# BSPD.net
KiCad netlist of a schematic drawn in Altium Designer
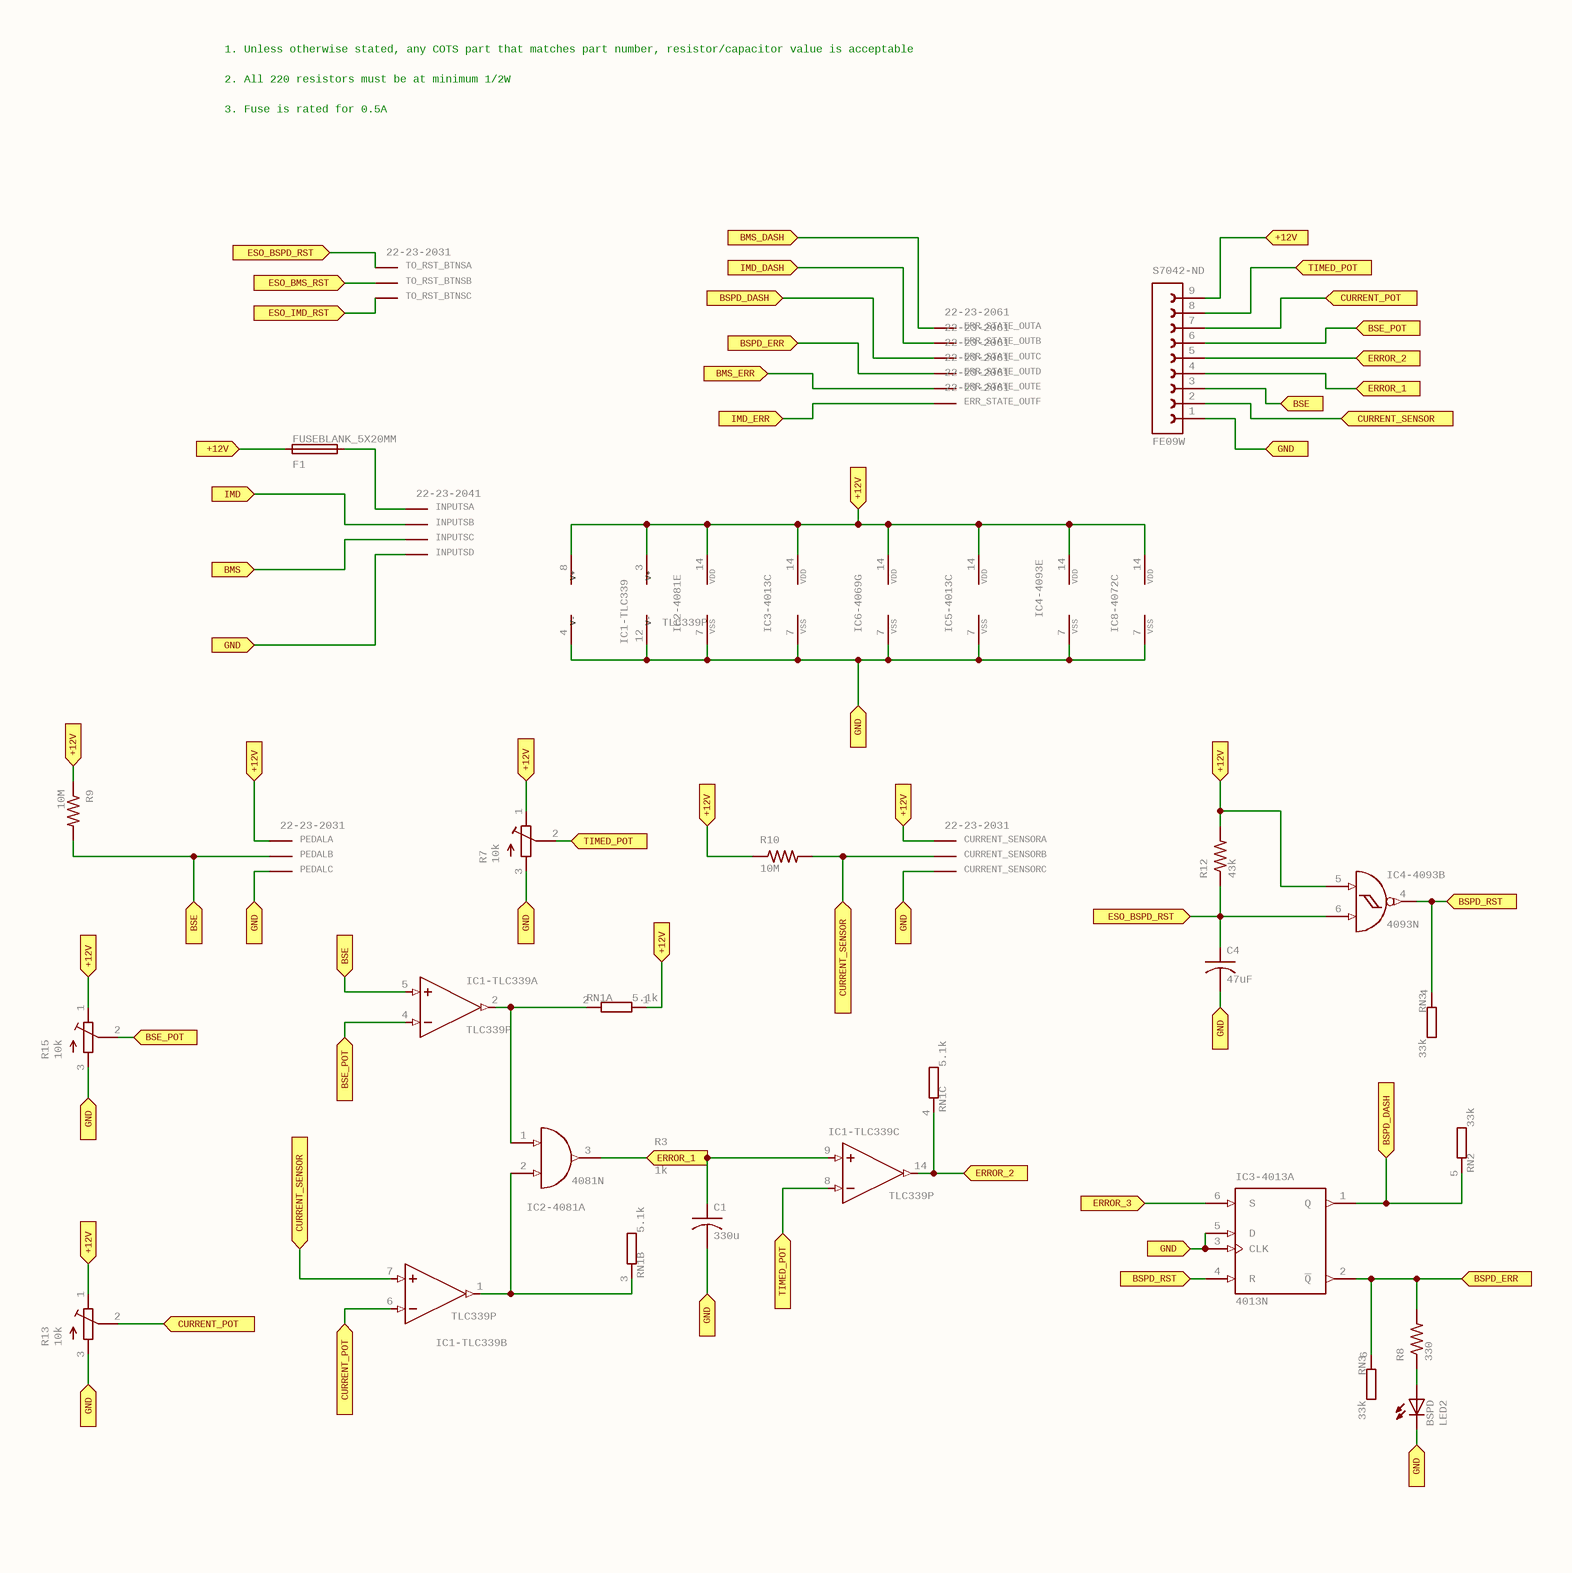
[diagram p0: BSPD.SchDoc, left]
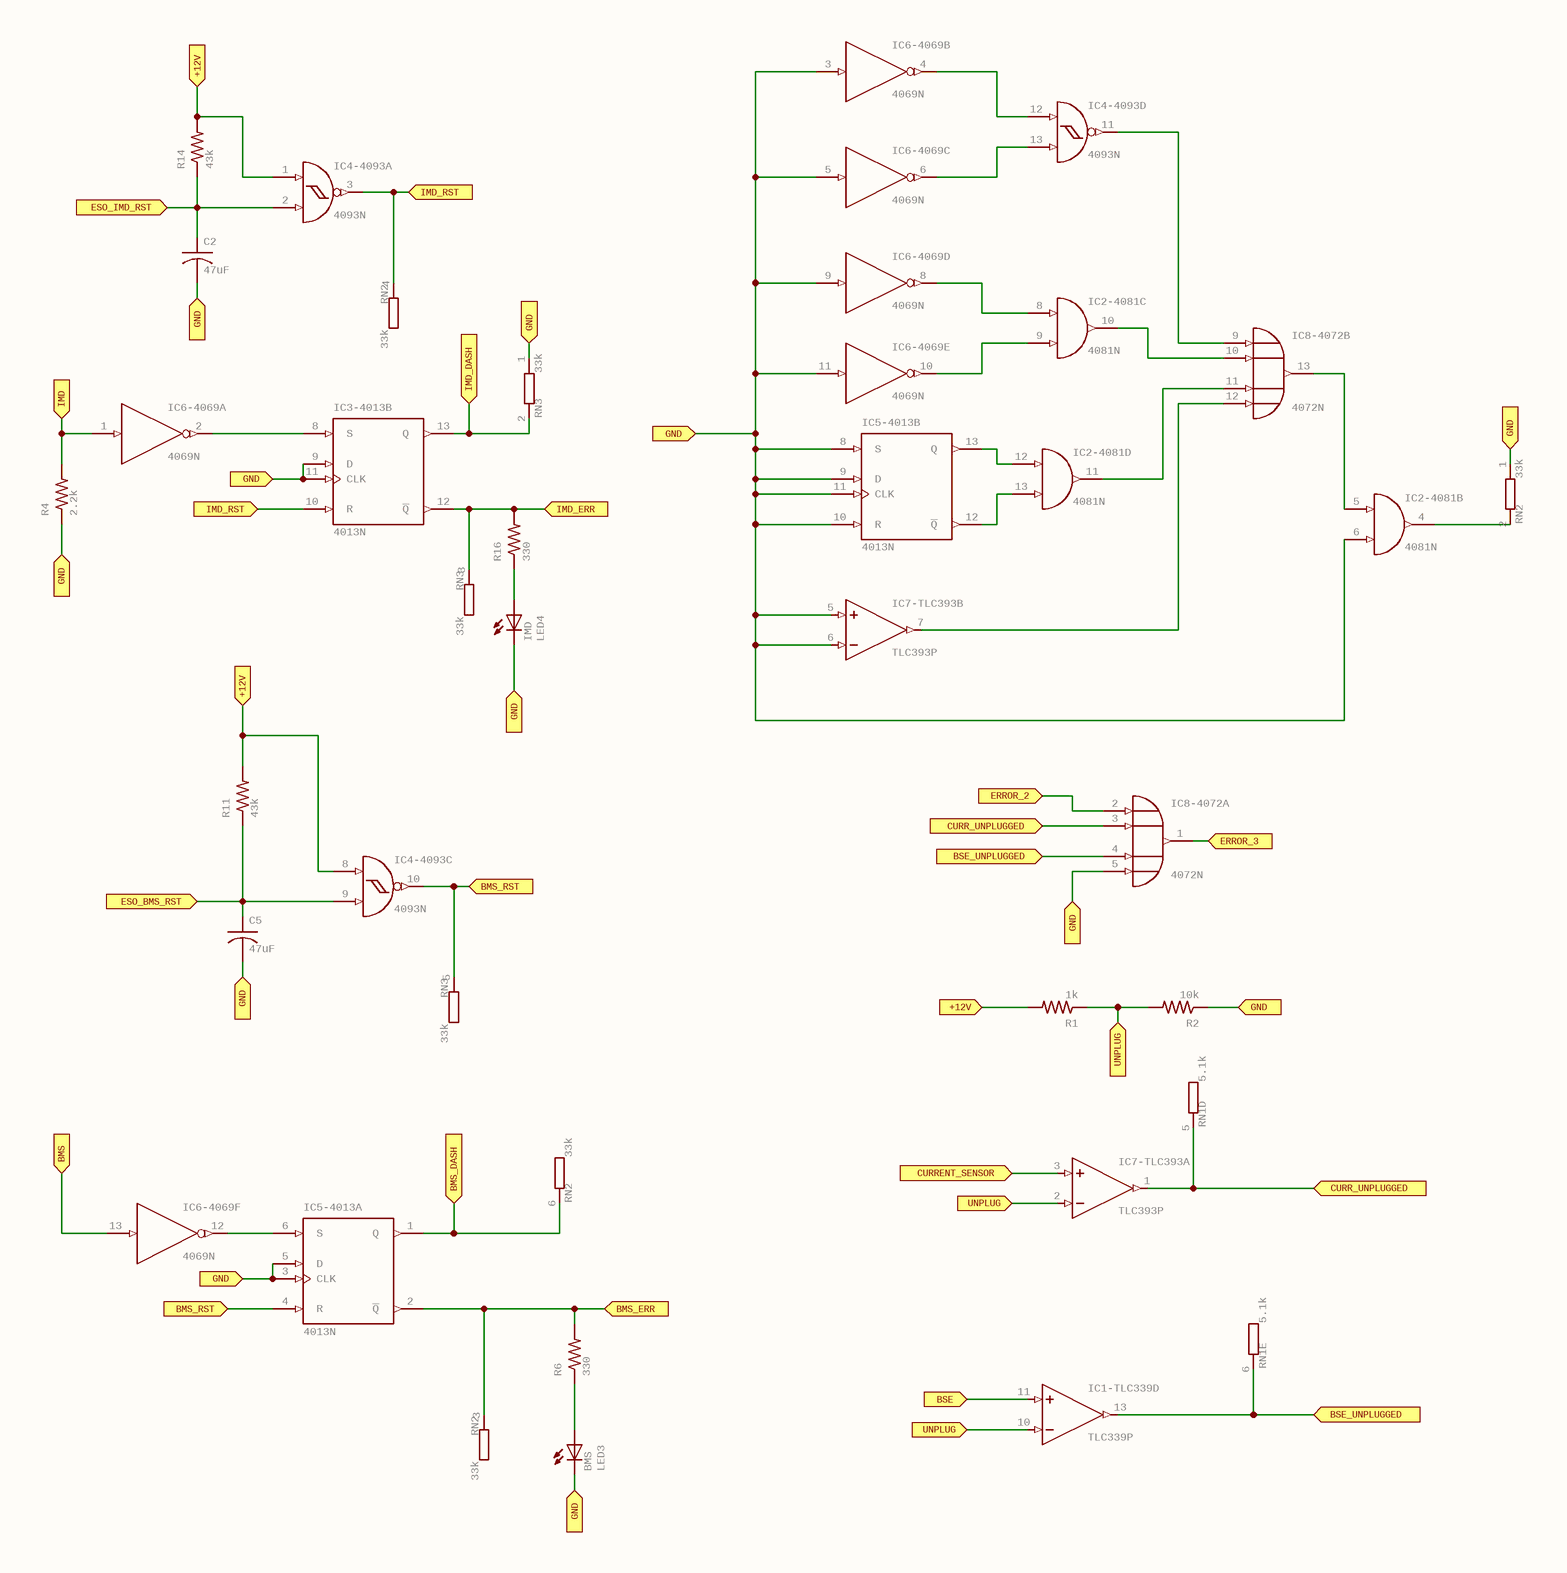
[diagram p1: BSPD.SchDoc, right]

(export (version "E")
  (design (tool "Eeschema 10.0.6"))
  (components
    (comp (ref "BMS") (value "LED3") (footprint "LED3MM") (libsource (lib "led") (part "LED3MM")))
    (comp (ref "BSPD") (value "LED2") (footprint "LED3MM") (libsource (lib "led") (part "LED3MM")))
    (comp (ref "C1")
      (value "330u")
      (footprint "C225-108X268")
      (description "CAPACITOR, American symbol")
      (libsource (lib "rcl") (part "C-US225-108X268"))
    )
    (comp (ref "C2")
      (value "47uF")
      (footprint "C050-024X044")
      (description "CAPACITOR, American symbol")
      (libsource (lib "rcl") (part "C-US050-024X044"))
    )
    (comp (ref "C4")
      (value "47uF")
      (footprint "C050-024X044")
      (description "CAPACITOR, American symbol")
      (libsource (lib "rcl") (part "C-US050-024X044"))
    )
    (comp (ref "C5")
      (value "47uF")
      (footprint "C050-024X044")
      (description "CAPACITOR, American symbol")
      (libsource (lib "rcl") (part "C-US050-024X044"))
    )
    (comp (ref "CURRENT_SENSOR")
      (value "22-23-2031")
      (footprint "22-23-2031")
      (description ".100\" (2.54mm) Center Header - 3 Pin")
      (fields (field (name "MF") "MOLEX"))
      (libsource (lib "con-molex") (part "22-23-2031"))
    )
    (comp (ref "ERR_STATE_OUT")
      (value "22-23-2061")
      (footprint "22-23-2061")
      (description ".100\" (2.54mm) Center Header - 6 Pin")
      (fields (field (name "MF") "MOLEX"))
      (libsource (lib "con-molex") (part "22-23-2061"))
    )
    (comp (ref "F1")
      (value "FUSEBLANK_5X20MM")
      (footprint "FUSE_HOLDER_5X20MM")
      (description "Fuse")
      (fields (field (name "MF") "MF") (field (name "MPN") "MPN"))
      (libsource (lib "fuse") (part "FUSEBLANK_5X20MM"))
    )
    (comp (ref "IC1-TLC339")
      (value "TLC339P")
      (footprint "DIL14")
      (description "COMPARATOR")
      (fields (field (name "V+") "V+") (field (name "V-") "V-"))
      (libsource (lib "linear") (part "TLC339P"))
    )
    (comp (ref "IC2-4081")
      (value "4081N")
      (footprint "DIL14")
      (description "Quad 2-input AND")
      (fields (field (name "VDD") "VDD") (field (name "VSS") "VSS"))
      (libsource (lib "40xx") (part "4081N"))
    )
    (comp (ref "IC3-4013")
      (value "4013N")
      (footprint "DIL14")
      (description "Dual D FLIP FLOP, set/reset")
      (fields (field (name "VDD") "VDD") (field (name "VSS") "VSS"))
      (libsource (lib "40xx") (part "4013N"))
    )
    (comp (ref "IC4-4093")
      (value "4093N")
      (footprint "DIL14")
      (description "Quad 2-input NAND schmitt trigger")
      (fields (field (name "VDD") "VDD") (field (name "VSS") "VSS"))
      (libsource (lib "40xx") (part "4093N"))
    )
    (comp (ref "IC5-4013")
      (value "4013N")
      (footprint "DIL14")
      (description "Dual D FLIP FLOP, set/reset")
      (fields (field (name "VDD") "VDD") (field (name "VSS") "VSS"))
      (libsource (lib "40xx") (part "4013N"))
    )
    (comp (ref "IC6-4069")
      (value "4069N")
      (footprint "DIL14")
      (description "Hex INVERTER")
      (fields (field (name "VDD") "VDD") (field (name "VSS") "VSS"))
      (libsource (lib "40xx") (part "4069N"))
    )
    (comp (ref "IC7-TLC393")
      (value "TLC393P")
      (footprint "DIL08")
      (description "COMPARATOR")
      (fields (field (name "V+") "V+") (field (name "V-") "V-"))
      (libsource (lib "linear") (part "TLC393P"))
    )
    (comp (ref "IC8-4072")
      (value "4072N")
      (footprint "DIL14")
      (description "Dual 4-input OR")
      (fields (field (name "VDD") "VDD") (field (name "VSS") "VSS"))
      (libsource (lib "40xx") (part "4072N"))
    )
    (comp (ref "IMD") (value "LED4") (footprint "LED3MM") (libsource (lib "led") (part "LED3MM")))
    (comp (ref "INPUTS")
      (value "22-23-2041")
      (footprint "22-23-2041")
      (description ".100\" (2.54mm) Center Header - 4 Pin")
      (fields (field (name "MF") "MOLEX"))
      (libsource (lib "con-molex") (part "22-23-2041"))
    )
    (comp (ref "PEDAL")
      (value "22-23-2031")
      (footprint "22-23-2031")
      (description ".100\" (2.54mm) Center Header - 3 Pin")
      (fields (field (name "MF") "MOLEX"))
      (libsource (lib "con-molex") (part "22-23-2031"))
    )
    (comp (ref "R1")
      (value "1k")
      (footprint "0207/12")
      (description "RESISTOR, American symbol")
      (libsource (lib "rcl") (part "R-US_0207/12"))
    )
    (comp (ref "R2")
      (value "10k")
      (footprint "0207/12")
      (description "RESISTOR, American symbol")
      (libsource (lib "rcl") (part "R-US_0207/12"))
    )
    (comp (ref "R3")
      (value "1k")
      (footprint "0207/12")
      (description "RESISTOR, American symbol")
      (libsource (lib "rcl") (part "R-US_0207/12"))
    )
    (comp (ref "R4")
      (value "2.2k")
      (footprint "0207/12")
      (description "RESISTOR, American symbol")
      (libsource (lib "rcl") (part "R-US_0207/12"))
    )
    (comp (ref "R6")
      (value "330")
      (footprint "0207/12")
      (description "RESISTOR, American symbol")
      (libsource (lib "rcl") (part "R-US_0207/12"))
    )
    (comp (ref "R7")
      (value "10k")
      (footprint "RTRIM3006P")
      (description "Trimm resistor")
      (libsource (lib "rcl") (part "R-TRIMM3006P"))
    )
    (comp (ref "R8")
      (value "330")
      (footprint "0207/12")
      (description "RESISTOR, American symbol")
      (libsource (lib "rcl") (part "R-US_0207/12"))
    )
    (comp (ref "R9")
      (value "10M")
      (footprint "0207/12")
      (description "RESISTOR, American symbol")
      (libsource (lib "rcl") (part "R-US_0207/12"))
    )
    (comp (ref "R10")
      (value "10M")
      (footprint "0207/12")
      (description "RESISTOR, American symbol")
      (libsource (lib "rcl") (part "R-US_0207/12"))
    )
    (comp (ref "R11")
      (value "43k")
      (footprint "0207/12")
      (description "RESISTOR, American symbol")
      (libsource (lib "rcl") (part "R-US_0207/12"))
    )
    (comp (ref "R12")
      (value "43k")
      (footprint "0207/12")
      (description "RESISTOR, American symbol")
      (libsource (lib "rcl") (part "R-US_0207/12"))
    )
    (comp (ref "R13")
      (value "10k")
      (footprint "RTRIM3006P")
      (description "Trimm resistor")
      (libsource (lib "rcl") (part "R-TRIMM3006P"))
    )
    (comp (ref "R14")
      (value "43k")
      (footprint "0207/12")
      (description "RESISTOR, American symbol")
      (libsource (lib "rcl") (part "R-US_0207/12"))
    )
    (comp (ref "R15")
      (value "10k")
      (footprint "RTRIM3006P")
      (description "Trimm resistor")
      (libsource (lib "rcl") (part "R-TRIMM3006P"))
    )
    (comp (ref "R16")
      (value "330")
      (footprint "0207/12")
      (description "RESISTOR, American symbol")
      (libsource (lib "rcl") (part "R-US_0207/12"))
    )
    (comp (ref "RN1")
      (value "5.1k")
      (footprint "SIL6")
      (description "SIL RESISTOR")
      (fields (field (name "MF") "MF") (field (name "MPN") "MPN"))
      (libsource (lib "resistor-sil") (part "GE05R"))
    )
    (comp (ref "RN2")
      (value "33k")
      (footprint "SIL6")
      (description "SIL RESISTOR")
      (fields (field (name "PART") "RN2") (field (name "MF") "MF") (field (name "MPN") "MPN"))
      (libsource (lib "resistor-sil") (part "GE05RP"))
    )
    (comp (ref "RN3")
      (value "33k")
      (footprint "SIL6")
      (description "SIL RESISTOR")
      (fields (field (name "PART") "RN3") (field (name "MF") "MF") (field (name "MPN") "MPN"))
      (libsource (lib "resistor-sil") (part "GE05RP"))
    )
    (comp (ref "S7042-ND")
      (value "FE09W")
      (footprint "FE09W")
      (description "FEMALE HEADER")
      (fields (field (name "MF") "MF") (field (name "MPN") "MPN") (field (name "LIBRARYNAME") "con-lsta"))
      (libsource (lib "con-lsta") (part "FE09W"))
    )
    (comp (ref "TO_RST_BTNS")
      (value "22-23-2031")
      (footprint "22-23-2031")
      (description ".100\" (2.54mm) Center Header - 3 Pin")
      (fields (field (name "MF") "MOLEX"))
      (libsource (lib "con-molex") (part "22-23-2031"))
    )
  )
  (nets
    (net (code "1") (name "/+12V") (class "Default")
      (node (ref "CURRENT_SENSOR") (pin "1") (pinfunction "S_1") (pintype "passive"))
      (node (ref "F1") (pin "1") (pinfunction "1_1") (pintype "passive"))
      (node (ref "IC1-TLC339") (pin "3") (pinfunction "V+_3") (pintype "power_in"))
      (node (ref "IC2-4081") (pin "14") (pinfunction "VDD_14") (pintype "power_in"))
      (node (ref "IC3-4013") (pin "14") (pinfunction "VDD_14") (pintype "power_in"))
      (node (ref "IC4-4093") (pin "1") (pinfunction "I0_1") (pintype "input"))
      (node (ref "IC4-4093") (pin "14") (pinfunction "VDD_14") (pintype "power_in"))
      (node (ref "IC4-4093") (pin "5") (pinfunction "I0_5") (pintype "input"))
      (node (ref "IC4-4093") (pin "8") (pinfunction "I0_8") (pintype "input"))
      (node (ref "IC5-4013") (pin "14") (pinfunction "VDD_14") (pintype "power_in"))
      (node (ref "IC6-4069") (pin "14") (pinfunction "VDD_14") (pintype "power_in"))
      (node (ref "IC7-TLC393") (pin "8") (pinfunction "V+_8") (pintype "power_in"))
      (node (ref "IC8-4072") (pin "14") (pinfunction "VDD_14") (pintype "power_in"))
      (node (ref "PEDAL") (pin "1") (pinfunction "S_1") (pintype "passive"))
      (node (ref "R1") (pin "2") (pinfunction "2_2") (pintype "passive"))
      (node (ref "R10") (pin "1") (pinfunction "1_1") (pintype "passive"))
      (node (ref "R11") (pin "2") (pinfunction "2_2") (pintype "passive"))
      (node (ref "R12") (pin "2") (pinfunction "2_2") (pintype "passive"))
      (node (ref "R13") (pin "1") (pinfunction "E_1") (pintype "passive"))
      (node (ref "R14") (pin "2") (pinfunction "2_2") (pintype "passive"))
      (node (ref "R15") (pin "1") (pinfunction "E_1") (pintype "passive"))
      (node (ref "R7") (pin "1") (pinfunction "E_1") (pintype "passive"))
      (node (ref "R9") (pin "1") (pinfunction "1_1") (pintype "passive"))
      (node (ref "RN1") (pin "1") (pinfunction "1_1") (pintype "passive"))
      (node (ref "S7042-ND") (pin "9") (pinfunction "9_9") (pintype "passive"))
    )
    (net (code "2") (name "/BMS") (class "Default")
      (node (ref "IC6-4069") (pin "13") (pinfunction "I_13") (pintype "input"))
      (node (ref "INPUTS") (pin "3") (pinfunction "S_3") (pintype "passive"))
    )
    (net (code "3") (name "/BMS_DASH") (class "Default")
      (node (ref "ERR_STATE_OUT") (pin "1") (pinfunction "S_1") (pintype "passive"))
      (node (ref "IC5-4013") (pin "1") (pinfunction "Q_1") (pintype "output"))
      (node (ref "RN2") (pin "6") (pinfunction "2_6") (pintype "passive"))
    )
    (net (code "4") (name "/BMS_ERR") (class "Default")
      (node (ref "ERR_STATE_OUT") (pin "5") (pinfunction "S_5") (pintype "passive"))
      (node (ref "IC5-4013") (pin "2") (pinfunction "~{Q}_2") (pintype "output"))
      (node (ref "R6") (pin "2") (pinfunction "2_2") (pintype "passive"))
      (node (ref "RN2") (pin "3") (pinfunction "2_3") (pintype "passive"))
    )
    (net (code "5") (name "/BMS_RST") (class "Default")
      (node (ref "IC4-4093") (pin "10") (pinfunction "O_10") (pintype "output"))
      (node (ref "IC5-4013") (pin "4") (pinfunction "R_4") (pintype "input"))
      (node (ref "RN3") (pin "5") (pinfunction "2_5") (pintype "passive"))
    )
    (net (code "6") (name "/BSE") (class "Default")
      (node (ref "IC1-TLC339") (pin "11") (pinfunction "+IN_11") (pintype "input"))
      (node (ref "IC1-TLC339") (pin "5") (pinfunction "+IN_5") (pintype "input"))
      (node (ref "PEDAL") (pin "2") (pinfunction "S_2") (pintype "passive"))
      (node (ref "R9") (pin "2") (pinfunction "2_2") (pintype "passive"))
      (node (ref "S7042-ND") (pin "3") (pinfunction "3_3") (pintype "passive"))
    )
    (net (code "7") (name "/BSE_POT") (class "Default")
      (node (ref "IC1-TLC339") (pin "4") (pinfunction "-IN_4") (pintype "input"))
      (node (ref "R15") (pin "2") (pinfunction "S_2") (pintype "passive"))
      (node (ref "S7042-ND") (pin "6") (pinfunction "6_6") (pintype "passive"))
    )
    (net (code "8") (name "/BSE_UNPLUGGED") (class "Default")
      (node (ref "IC1-TLC339") (pin "13") (pinfunction "OUT_13") (pintype "output"))
      (node (ref "IC8-4072") (pin "4") (pinfunction "I2_4") (pintype "input"))
      (node (ref "RN1") (pin "6") (pinfunction "2_6") (pintype "passive"))
    )
    (net (code "9") (name "/BSPD_DASH") (class "Default")
      (node (ref "ERR_STATE_OUT") (pin "3") (pinfunction "S_3") (pintype "passive"))
      (node (ref "IC3-4013") (pin "1") (pinfunction "Q_1") (pintype "output"))
      (node (ref "RN2") (pin "5") (pinfunction "2_5") (pintype "passive"))
    )
    (net (code "10") (name "/BSPD_ERR") (class "Default")
      (node (ref "ERR_STATE_OUT") (pin "4") (pinfunction "S_4") (pintype "passive"))
      (node (ref "IC3-4013") (pin "2") (pinfunction "~{Q}_2") (pintype "output"))
      (node (ref "R8") (pin "2") (pinfunction "2_2") (pintype "passive"))
      (node (ref "RN3") (pin "6") (pinfunction "2_6") (pintype "passive"))
    )
    (net (code "11") (name "/BSPD_RST") (class "Default")
      (node (ref "IC3-4013") (pin "4") (pinfunction "R_4") (pintype "input"))
      (node (ref "IC4-4093") (pin "4") (pinfunction "O_4") (pintype "output"))
      (node (ref "RN3") (pin "4") (pinfunction "2_4") (pintype "passive"))
    )
    (net (code "12") (name "/CURRENT_POT") (class "Default")
      (node (ref "IC1-TLC339") (pin "6") (pinfunction "-IN_6") (pintype "input"))
      (node (ref "R13") (pin "2") (pinfunction "S_2") (pintype "passive"))
      (node (ref "S7042-ND") (pin "7") (pinfunction "7_7") (pintype "passive"))
    )
    (net (code "13") (name "/CURRENT_SENSOR") (class "Default")
      (node (ref "CURRENT_SENSOR") (pin "2") (pinfunction "S_2") (pintype "passive"))
      (node (ref "IC1-TLC339") (pin "7") (pinfunction "+IN_7") (pintype "input"))
      (node (ref "IC7-TLC393") (pin "3") (pinfunction "+IN_3") (pintype "input"))
      (node (ref "R10") (pin "2") (pinfunction "2_2") (pintype "passive"))
      (node (ref "S7042-ND") (pin "2") (pinfunction "2_2") (pintype "passive"))
    )
    (net (code "14") (name "/CURR_UNPLUGGED") (class "Default")
      (node (ref "IC7-TLC393") (pin "1") (pinfunction "OUT_1") (pintype "output"))
      (node (ref "IC8-4072") (pin "3") (pinfunction "I1_3") (pintype "input"))
      (node (ref "RN1") (pin "5") (pinfunction "2_5") (pintype "passive"))
    )
    (net (code "15") (name "/ERROR_1") (class "Default")
      (node (ref "C1") (pin "1") (pinfunction "1_1") (pintype "passive"))
      (node (ref "IC1-TLC339") (pin "9") (pinfunction "+IN_9") (pintype "input"))
      (node (ref "IC2-4081") (pin "3") (pinfunction "O_3") (pintype "output"))
      (node (ref "R3") (pin "1") (pinfunction "1_1") (pintype "passive"))
      (node (ref "R3") (pin "2") (pinfunction "2_2") (pintype "passive"))
      (node (ref "S7042-ND") (pin "4") (pinfunction "4_4") (pintype "passive"))
    )
    (net (code "16") (name "/ERROR_2") (class "Default")
      (node (ref "IC1-TLC339") (pin "14") (pinfunction "OUT_14") (pintype "output"))
      (node (ref "IC8-4072") (pin "2") (pinfunction "I0_2") (pintype "input"))
      (node (ref "RN1") (pin "4") (pinfunction "2_4") (pintype "passive"))
      (node (ref "S7042-ND") (pin "5") (pinfunction "5_5") (pintype "passive"))
    )
    (net (code "17") (name "/ERROR_3") (class "Default")
      (node (ref "IC3-4013") (pin "6") (pinfunction "S_6") (pintype "input"))
      (node (ref "IC8-4072") (pin "1") (pinfunction "O_1") (pintype "output"))
    )
    (net (code "18") (name "/ESO_BMS_RST") (class "Default")
      (node (ref "C5") (pin "1") (pinfunction "1_1") (pintype "passive"))
      (node (ref "IC4-4093") (pin "9") (pinfunction "I1_9") (pintype "input"))
      (node (ref "R11") (pin "1") (pinfunction "1_1") (pintype "passive"))
      (node (ref "TO_RST_BTNS") (pin "2") (pinfunction "S_2") (pintype "passive"))
    )
    (net (code "19") (name "/ESO_BSPD_RST") (class "Default")
      (node (ref "C4") (pin "1") (pinfunction "1_1") (pintype "passive"))
      (node (ref "IC4-4093") (pin "6") (pinfunction "I1_6") (pintype "input"))
      (node (ref "R12") (pin "1") (pinfunction "1_1") (pintype "passive"))
      (node (ref "TO_RST_BTNS") (pin "1") (pinfunction "S_1") (pintype "passive"))
    )
    (net (code "20") (name "/ESO_IMD_RST") (class "Default")
      (node (ref "C2") (pin "1") (pinfunction "1_1") (pintype "passive"))
      (node (ref "IC4-4093") (pin "2") (pinfunction "I1_2") (pintype "input"))
      (node (ref "R14") (pin "1") (pinfunction "1_1") (pintype "passive"))
      (node (ref "TO_RST_BTNS") (pin "3") (pinfunction "S_3") (pintype "passive"))
    )
    (net (code "21") (name "/GND") (class "Default")
      (node (ref "BMS") (pin "K") (pinfunction "C_K") (pintype "passive"))
      (node (ref "BSPD") (pin "K") (pinfunction "C_K") (pintype "passive"))
      (node (ref "C1") (pin "2") (pinfunction "2_2") (pintype "passive"))
      (node (ref "C2") (pin "2") (pinfunction "2_2") (pintype "passive"))
      (node (ref "C4") (pin "2") (pinfunction "2_2") (pintype "passive"))
      (node (ref "C5") (pin "2") (pinfunction "2_2") (pintype "passive"))
      (node (ref "CURRENT_SENSOR") (pin "3") (pinfunction "S_3") (pintype "passive"))
      (node (ref "IC1-TLC339") (pin "12") (pinfunction "V-_12") (pintype "power_in"))
      (node (ref "IC2-4081") (pin "6") (pinfunction "I1_6") (pintype "input"))
      (node (ref "IC2-4081") (pin "7") (pinfunction "VSS_7") (pintype "power_in"))
      (node (ref "IC3-4013") (pin "11") (pinfunction "CLK_11") (pintype "input"))
      (node (ref "IC3-4013") (pin "3") (pinfunction "CLK_3") (pintype "input"))
      (node (ref "IC3-4013") (pin "5") (pinfunction "D_5") (pintype "input"))
      (node (ref "IC3-4013") (pin "7") (pinfunction "VSS_7") (pintype "power_in"))
      (node (ref "IC3-4013") (pin "9") (pinfunction "D_9") (pintype "input"))
      (node (ref "IC4-4093") (pin "7") (pinfunction "VSS_7") (pintype "power_in"))
      (node (ref "IC5-4013") (pin "10") (pinfunction "R_10") (pintype "input"))
      (node (ref "IC5-4013") (pin "11") (pinfunction "CLK_11") (pintype "input"))
      (node (ref "IC5-4013") (pin "3") (pinfunction "CLK_3") (pintype "input"))
      (node (ref "IC5-4013") (pin "5") (pinfunction "D_5") (pintype "input"))
      (node (ref "IC5-4013") (pin "7") (pinfunction "VSS_7") (pintype "power_in"))
      (node (ref "IC5-4013") (pin "8") (pinfunction "S_8") (pintype "input"))
      (node (ref "IC5-4013") (pin "9") (pinfunction "D_9") (pintype "input"))
      (node (ref "IC6-4069") (pin "11") (pinfunction "I_11") (pintype "input"))
      (node (ref "IC6-4069") (pin "3") (pinfunction "I_3") (pintype "input"))
      (node (ref "IC6-4069") (pin "5") (pinfunction "I_5") (pintype "input"))
      (node (ref "IC6-4069") (pin "7") (pinfunction "VSS_7") (pintype "power_in"))
      (node (ref "IC6-4069") (pin "9") (pinfunction "I_9") (pintype "input"))
      (node (ref "IC7-TLC393") (pin "4") (pinfunction "V-_4") (pintype "power_in"))
      (node (ref "IC7-TLC393") (pin "5") (pinfunction "+IN_5") (pintype "input"))
      (node (ref "IC7-TLC393") (pin "6") (pinfunction "-IN_6") (pintype "input"))
      (node (ref "IC8-4072") (pin "5") (pinfunction "I3_5") (pintype "input"))
      (node (ref "IC8-4072") (pin "7") (pinfunction "VSS_7") (pintype "power_in"))
      (node (ref "IMD") (pin "K") (pinfunction "C_K") (pintype "passive"))
      (node (ref "INPUTS") (pin "4") (pinfunction "S_4") (pintype "passive"))
      (node (ref "PEDAL") (pin "3") (pinfunction "S_3") (pintype "passive"))
      (node (ref "R13") (pin "3") (pinfunction "A_3") (pintype "passive"))
      (node (ref "R15") (pin "3") (pinfunction "A_3") (pintype "passive"))
      (node (ref "R2") (pin "1") (pinfunction "1_1") (pintype "passive"))
      (node (ref "R4") (pin "1") (pinfunction "1_1") (pintype "passive"))
      (node (ref "R7") (pin "3") (pinfunction "A_3") (pintype "passive"))
      (node (ref "RN2") (pin "1") (pinfunction "1_1") (pintype "passive"))
      (node (ref "RN3") (pin "1") (pinfunction "1_1") (pintype "passive"))
      (node (ref "S7042-ND") (pin "1") (pinfunction "1_1") (pintype "passive"))
    )
    (net (code "22") (name "/IMD") (class "Default")
      (node (ref "IC6-4069") (pin "1") (pinfunction "I_1") (pintype "input"))
      (node (ref "INPUTS") (pin "2") (pinfunction "S_2") (pintype "passive"))
      (node (ref "R4") (pin "2") (pinfunction "2_2") (pintype "passive"))
    )
    (net (code "23") (name "/IMD_DASH") (class "Default")
      (node (ref "ERR_STATE_OUT") (pin "2") (pinfunction "S_2") (pintype "passive"))
      (node (ref "IC3-4013") (pin "13") (pinfunction "Q_13") (pintype "output"))
      (node (ref "RN3") (pin "2") (pinfunction "2_2") (pintype "passive"))
    )
    (net (code "24") (name "/IMD_ERR") (class "Default")
      (node (ref "ERR_STATE_OUT") (pin "6") (pinfunction "S_6") (pintype "passive"))
      (node (ref "IC3-4013") (pin "12") (pinfunction "~{Q}_12") (pintype "output"))
      (node (ref "R16") (pin "2") (pinfunction "2_2") (pintype "passive"))
      (node (ref "RN3") (pin "3") (pinfunction "2_3") (pintype "passive"))
    )
    (net (code "25") (name "/IMD_RST") (class "Default")
      (node (ref "IC3-4013") (pin "10") (pinfunction "R_10") (pintype "input"))
      (node (ref "IC4-4093") (pin "3") (pinfunction "O_3") (pintype "output"))
      (node (ref "RN2") (pin "4") (pinfunction "2_4") (pintype "passive"))
    )
    (net (code "26") (name "/TIMED_POT") (class "Default")
      (node (ref "IC1-TLC339") (pin "8") (pinfunction "-IN_8") (pintype "input"))
      (node (ref "R7") (pin "2") (pinfunction "S_2") (pintype "passive"))
      (node (ref "S7042-ND") (pin "8") (pinfunction "8_8") (pintype "passive"))
    )
    (net (code "27") (name "/UNPLUG") (class "Default")
      (node (ref "IC1-TLC339") (pin "10") (pinfunction "-IN_10") (pintype "input"))
      (node (ref "IC7-TLC393") (pin "2") (pinfunction "-IN_2") (pintype "input"))
      (node (ref "R1") (pin "1") (pinfunction "1_1") (pintype "passive"))
      (node (ref "R2") (pin "2") (pinfunction "2_2") (pintype "passive"))
    )
    (net (code "28") (name "Net-(BMS-PadA)") (class "Default")
      (node (ref "BMS") (pin "A") (pinfunction "A_A") (pintype "passive"))
      (node (ref "R6") (pin "1") (pinfunction "1_1") (pintype "passive"))
    )
    (net (code "29") (name "Net-(BSPD-PadA)") (class "Default")
      (node (ref "BSPD") (pin "A") (pinfunction "A_A") (pintype "passive"))
      (node (ref "R8") (pin "1") (pinfunction "1_1") (pintype "passive"))
    )
    (net (code "30") (name "Net-(IC1-TLC339A-OUT)") (class "Default")
      (node (ref "IC1-TLC339") (pin "2") (pinfunction "OUT_2") (pintype "output"))
      (node (ref "IC2-4081") (pin "1") (pinfunction "I0_1") (pintype "input"))
      (node (ref "RN1") (pin "2") (pinfunction "2_2") (pintype "passive"))
    )
    (net (code "31") (name "Net-(IC1-TLC339B-OUT)") (class "Default")
      (node (ref "IC1-TLC339") (pin "1") (pinfunction "OUT_1") (pintype "output"))
      (node (ref "IC2-4081") (pin "2") (pinfunction "I1_2") (pintype "input"))
      (node (ref "RN1") (pin "3") (pinfunction "2_3") (pintype "passive"))
    )
    (net (code "32") (name "Net-(IC2-4081B-I0)") (class "Default")
      (node (ref "IC2-4081") (pin "5") (pinfunction "I0_5") (pintype "input"))
      (node (ref "IC8-4072") (pin "13") (pinfunction "O_13") (pintype "output"))
    )
    (net (code "33") (name "Net-(IC2-4081B-O)") (class "Default")
      (node (ref "IC2-4081") (pin "4") (pinfunction "O_4") (pintype "output"))
      (node (ref "RN2") (pin "2") (pinfunction "2_2") (pintype "passive"))
    )
    (net (code "34") (name "Net-(IC2-4081C-I0)") (class "Default")
      (node (ref "IC2-4081") (pin "8") (pinfunction "I0_8") (pintype "input"))
      (node (ref "IC6-4069") (pin "8") (pinfunction "O_8") (pintype "output"))
    )
    (net (code "35") (name "Net-(IC2-4081C-I1)") (class "Default")
      (node (ref "IC2-4081") (pin "9") (pinfunction "I1_9") (pintype "input"))
      (node (ref "IC6-4069") (pin "10") (pinfunction "O_10") (pintype "output"))
    )
    (net (code "36") (name "Net-(IC2-4081C-O)") (class "Default")
      (node (ref "IC2-4081") (pin "10") (pinfunction "O_10") (pintype "output"))
      (node (ref "IC8-4072") (pin "10") (pinfunction "I1_10") (pintype "input"))
    )
    (net (code "37") (name "Net-(IC2-4081D-I0)") (class "Default")
      (node (ref "IC2-4081") (pin "12") (pinfunction "I0_12") (pintype "input"))
      (node (ref "IC5-4013") (pin "13") (pinfunction "Q_13") (pintype "output"))
    )
    (net (code "38") (name "Net-(IC2-4081D-I1)") (class "Default")
      (node (ref "IC2-4081") (pin "13") (pinfunction "I1_13") (pintype "input"))
      (node (ref "IC5-4013") (pin "12") (pinfunction "~{Q}_12") (pintype "output"))
    )
    (net (code "39") (name "Net-(IC2-4081D-O)") (class "Default")
      (node (ref "IC2-4081") (pin "11") (pinfunction "O_11") (pintype "output"))
      (node (ref "IC8-4072") (pin "11") (pinfunction "I2_11") (pintype "input"))
    )
    (net (code "40") (name "Net-(IC3-4013B-S)") (class "Default")
      (node (ref "IC3-4013") (pin "8") (pinfunction "S_8") (pintype "input"))
      (node (ref "IC6-4069") (pin "2") (pinfunction "O_2") (pintype "output"))
    )
    (net (code "41") (name "Net-(IC4-4093D-I0)") (class "Default")
      (node (ref "IC4-4093") (pin "12") (pinfunction "I0_12") (pintype "input"))
      (node (ref "IC6-4069") (pin "4") (pinfunction "O_4") (pintype "output"))
    )
    (net (code "42") (name "Net-(IC4-4093D-I1)") (class "Default")
      (node (ref "IC4-4093") (pin "13") (pinfunction "I1_13") (pintype "input"))
      (node (ref "IC6-4069") (pin "6") (pinfunction "O_6") (pintype "output"))
    )
    (net (code "43") (name "Net-(IC4-4093D-O)") (class "Default")
      (node (ref "IC4-4093") (pin "11") (pinfunction "O_11") (pintype "output"))
      (node (ref "IC8-4072") (pin "9") (pinfunction "I0_9") (pintype "input"))
    )
    (net (code "44") (name "Net-(IC5-4013A-S)") (class "Default")
      (node (ref "IC5-4013") (pin "6") (pinfunction "S_6") (pintype "input"))
      (node (ref "IC6-4069") (pin "12") (pinfunction "O_12") (pintype "output"))
    )
    (net (code "45") (name "Net-(IC7-TLC393B-OUT)") (class "Default")
      (node (ref "IC7-TLC393") (pin "7") (pinfunction "OUT_7") (pintype "output"))
      (node (ref "IC8-4072") (pin "12") (pinfunction "I3_12") (pintype "input"))
    )
    (net (code "46") (name "Net-(IMD-PadA)") (class "Default")
      (node (ref "IMD") (pin "A") (pinfunction "A_A") (pintype "passive"))
      (node (ref "R16") (pin "1") (pinfunction "1_1") (pintype "passive"))
    )
    (net (code "47") (name "Net-(INPUTSA-S)") (class "Default")
      (node (ref "F1") (pin "2") (pinfunction "2_2") (pintype "passive"))
      (node (ref "INPUTS") (pin "1") (pinfunction "S_1") (pintype "passive"))
    )
  )
)
